# FlowSensor2.net
KiCad netlist of a schematic drawn in EAGLE
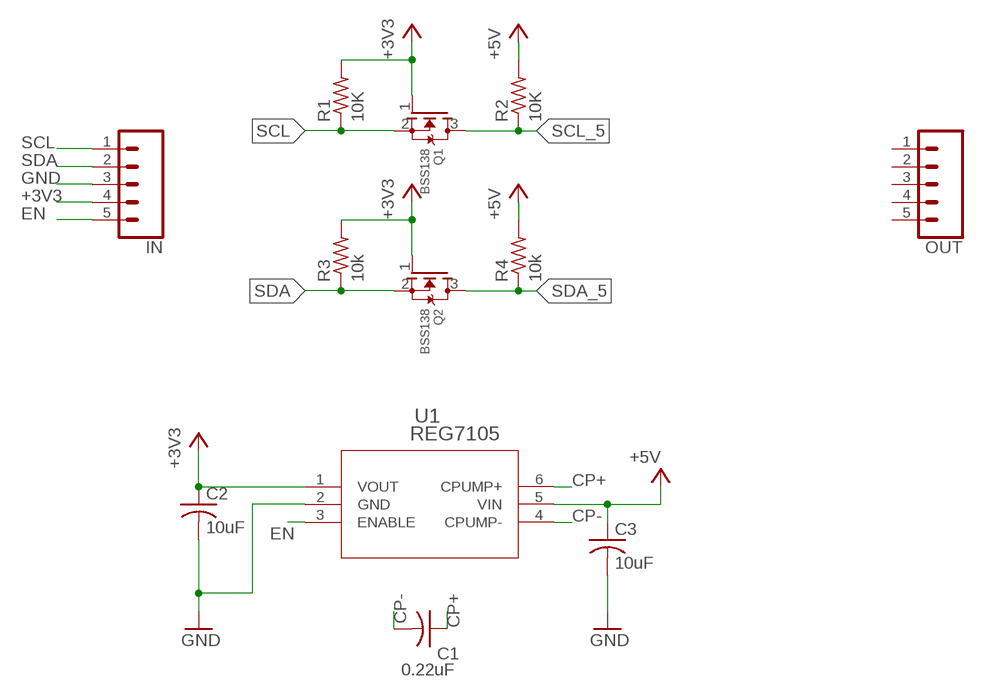
[diagram p0: schematic, sheet 1]

(export (version "E")
  (design (tool "Eeschema 10.0.6"))
  (components
    (comp (ref "C1")
      (value "0.22uF")
      (footprint "eagle-import:C0805K")
      (libsource (lib "eagle-import") (part "C-USC0805K"))
    )
    (comp (ref "C2")
      (value "10uF")
      (footprint "eagle-import:C0805K")
      (libsource (lib "eagle-import") (part "C-USC0805K"))
    )
    (comp (ref "C3")
      (value "10uF")
      (footprint "eagle-import:C0805K")
      (libsource (lib "eagle-import") (part "C-USC0805K"))
    )
    (comp (ref "IN")
      (value "CONN_05PTH_LONGPADS")
      (footprint "eagle-import:1X05_LONGPADS")
      (libsource (lib "eagle-import") (part "CONN_05PTH_LONGPADS"))
    )
    (comp (ref "OUT")
      (value "CONN_05PTH_LONGPADS")
      (footprint "eagle-import:1X05_LONGPADS")
      (libsource (lib "eagle-import") (part "CONN_05PTH_LONGPADS"))
    )
    (comp (ref "Q1")
      (value "BSS138")
      (footprint "eagle-import:SOT23")
      (libsource (lib "eagle-import") (part "MOSFET-NREFLOW"))
    )
    (comp (ref "Q2")
      (value "BSS138")
      (footprint "eagle-import:SOT23")
      (libsource (lib "eagle-import") (part "MOSFET-NREFLOW"))
    )
    (comp (ref "R1")
      (value "10K")
      (footprint "eagle-import:R1206")
      (libsource (lib "eagle-import") (part "R-US_R1206"))
    )
    (comp (ref "R2")
      (value "10K")
      (footprint "eagle-import:R1206")
      (libsource (lib "eagle-import") (part "R-US_R1206"))
    )
    (comp (ref "R3")
      (value "10k")
      (footprint "eagle-import:R1206")
      (libsource (lib "eagle-import") (part "R-US_R1206"))
    )
    (comp (ref "R4")
      (value "10k")
      (footprint "eagle-import:R1206")
      (libsource (lib "eagle-import") (part "R-US_R1206"))
    )
    (comp (ref "U1")
      (value "REG7105")
      (footprint "eagle-import:DDC6-M")
      (fields
        (field (name "GENERIC_PART_NUMBER") "REG71050")
        (field (name "MANUFACTURER") "Texas Instruments")
        (field (name "MANUFACTURER_PART_NUMBER") "REG71050DDCR")
      )
      (libsource (lib "eagle-import") (part "REG71050DDCRDDC6-M"))
    )
  )
  (nets
    (net (code "1") (name "+3V3") (class "Default")
      (node (ref "C2") (pin "1") (pinfunction "1_1") (pintype "passive"))
      (node (ref "IN") (pin "4") (pinfunction "4_4") (pintype "passive"))
      (node (ref "Q1") (pin "1") (pinfunction "G_1") (pintype "bidirectional"))
      (node (ref "Q2") (pin "1") (pinfunction "G_1") (pintype "bidirectional"))
      (node (ref "R1") (pin "2") (pinfunction "2_2") (pintype "passive"))
      (node (ref "R3") (pin "2") (pinfunction "2_2") (pintype "passive"))
      (node (ref "U1") (pin "1") (pinfunction "VOUT_1") (pintype "output"))
    )
    (net (code "2") (name "+5V") (class "Default")
      (node (ref "C3") (pin "1") (pinfunction "1_1") (pintype "passive"))
      (node (ref "R2") (pin "2") (pinfunction "2_2") (pintype "passive"))
      (node (ref "R4") (pin "2") (pinfunction "2_2") (pintype "passive"))
      (node (ref "U1") (pin "5") (pinfunction "VIN_5") (pintype "input"))
    )
    (net (code "3") (name "/CP+") (class "Default")
      (node (ref "C1") (pin "1") (pinfunction "1_1") (pintype "passive"))
      (node (ref "U1") (pin "6") (pinfunction "CPUMP+_6") (pintype "passive"))
    )
    (net (code "4") (name "/CP-") (class "Default")
      (node (ref "C1") (pin "2") (pinfunction "2_2") (pintype "passive"))
      (node (ref "U1") (pin "4") (pinfunction "CPUMP-_4") (pintype "passive"))
    )
    (net (code "5") (name "/EN") (class "Default")
      (node (ref "IN") (pin "5") (pinfunction "5_5") (pintype "passive"))
      (node (ref "U1") (pin "3") (pinfunction "ENABLE_3") (pintype "passive"))
    )
    (net (code "6") (name "GND") (class "Default")
      (node (ref "C2") (pin "2") (pinfunction "2_2") (pintype "passive"))
      (node (ref "C3") (pin "2") (pinfunction "2_2") (pintype "passive"))
      (node (ref "IN") (pin "3") (pinfunction "3_3") (pintype "passive"))
      (node (ref "U1") (pin "2") (pinfunction "GND_2") (pintype "power_in"))
    )
    (net (code "7") (name "SCL") (class "Default")
      (node (ref "IN") (pin "1") (pinfunction "1_1") (pintype "passive"))
      (node (ref "Q1") (pin "2") (pinfunction "S_2") (pintype "bidirectional"))
      (node (ref "R1") (pin "1") (pinfunction "1_1") (pintype "passive"))
    )
    (net (code "8") (name "SCL_5") (class "Default")
      (node (ref "Q1") (pin "3") (pinfunction "D_3") (pintype "bidirectional"))
      (node (ref "R2") (pin "1") (pinfunction "1_1") (pintype "passive"))
    )
    (net (code "9") (name "SDA") (class "Default")
      (node (ref "IN") (pin "2") (pinfunction "2_2") (pintype "passive"))
      (node (ref "Q2") (pin "2") (pinfunction "S_2") (pintype "bidirectional"))
      (node (ref "R3") (pin "1") (pinfunction "1_1") (pintype "passive"))
    )
    (net (code "10") (name "SDA_5") (class "Default")
      (node (ref "Q2") (pin "3") (pinfunction "D_3") (pintype "bidirectional"))
      (node (ref "R4") (pin "1") (pinfunction "1_1") (pintype "passive"))
    )
    (net (code "11") (name "unconnected-(OUT-Pad1)") (class "Default")
      (node (ref "OUT") (pin "1") (pinfunction "1_1") (pintype "passive"))
    )
    (net (code "12") (name "unconnected-(OUT-Pad2)") (class "Default")
      (node (ref "OUT") (pin "2") (pinfunction "2_2") (pintype "passive"))
    )
    (net (code "13") (name "unconnected-(OUT-Pad3)") (class "Default")
      (node (ref "OUT") (pin "3") (pinfunction "3_3") (pintype "passive"))
    )
    (net (code "14") (name "unconnected-(OUT-Pad4)") (class "Default")
      (node (ref "OUT") (pin "4") (pinfunction "4_4") (pintype "passive"))
    )
    (net (code "15") (name "unconnected-(OUT-Pad5)") (class "Default")
      (node (ref "OUT") (pin "5") (pinfunction "5_5") (pintype "passive"))
    )
  )
)
